# PlantMonitor.net
KiCad netlist of a schematic drawn in EAGLE
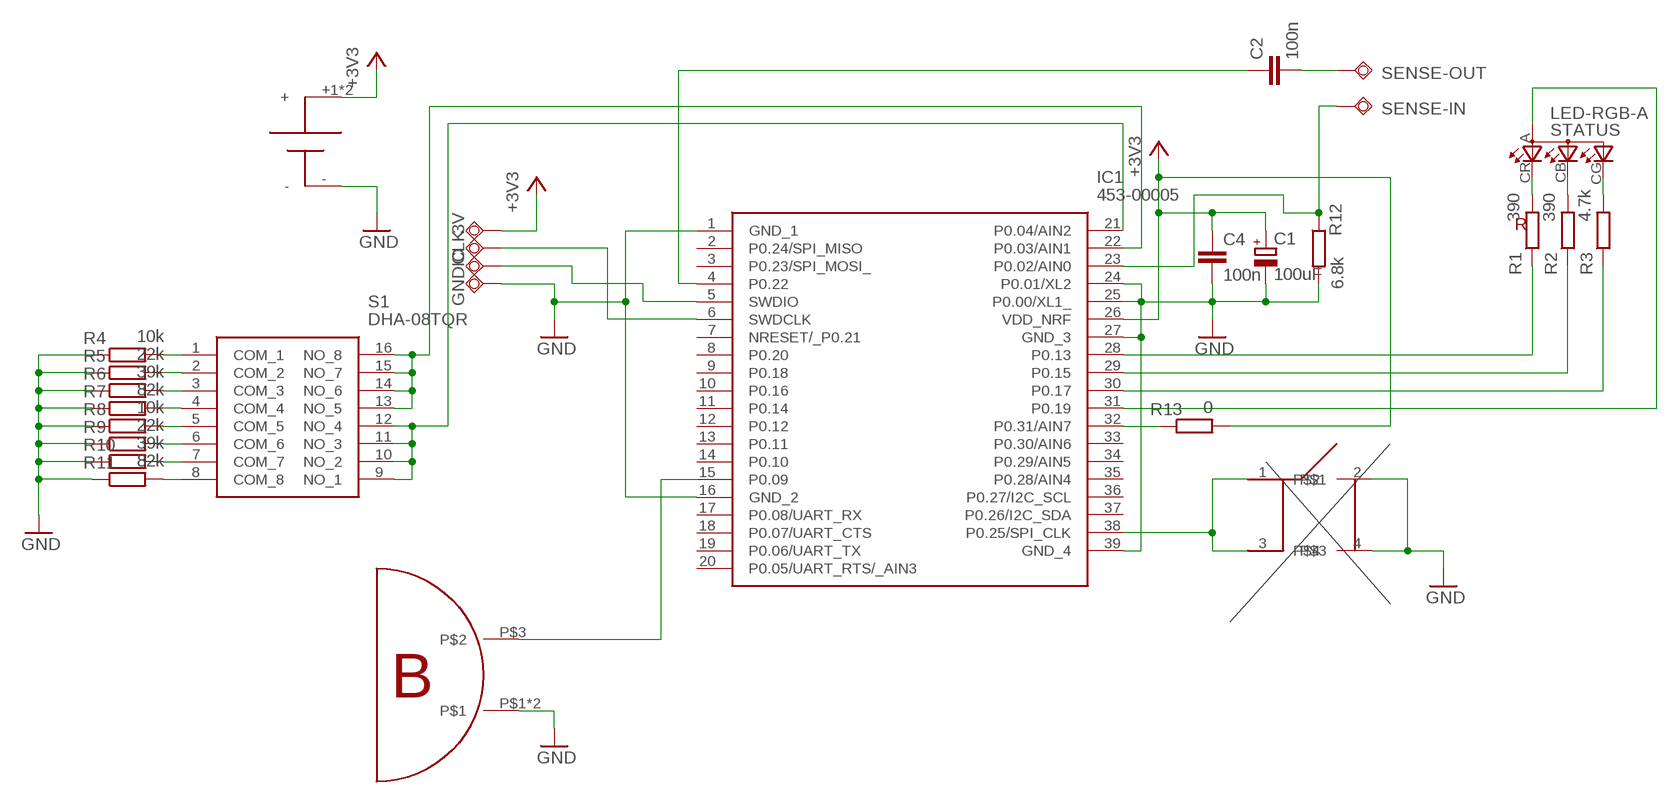
[diagram p0: schematic, sheet 1]

(export (version "E")
  (design (tool "Eeschema 10.0.6"))
  (components
    (comp (ref "3V")
      (value "TPSQB1,27")
      (footprint "eagle-import:B1,27")
      (libsource (lib "eagle-import") (part "TPSQB1,27"))
    )
    (comp (ref "C1")
      (value "100uF")
      (footprint "eagle-import:A_3216-18W")
      (libsource (lib "eagle-import") (part "CPOL-EUA/3216-18W"))
    )
    (comp (ref "C2")
      (value "100n")
      (footprint "eagle-import:C0603K")
      (libsource (lib "eagle-import") (part "C-EUC0603K"))
    )
    (comp (ref "C4")
      (value "100n")
      (footprint "eagle-import:C0603K")
      (libsource (lib "eagle-import") (part "C-EUC0603K"))
    )
    (comp (ref "CLK")
      (value "TPSQB1,27")
      (footprint "eagle-import:B1,27")
      (libsource (lib "eagle-import") (part "TPSQB1,27"))
    )
    (comp (ref "GND")
      (value "TPSQB1,27")
      (footprint "eagle-import:B1,27")
      (libsource (lib "eagle-import") (part "TPSQB1,27"))
    )
    (comp (ref "IC1")
      (value "453-00005")
      (footprint "eagle-import:45300005")
      (fields (field (name "MOUSER_PART_NUMBER") "239-453-00005"))
      (libsource (lib "eagle-import") (part "453-00005"))
    )
    (comp (ref "IO")
      (value "TPSQB1,27")
      (footprint "eagle-import:B1,27")
      (libsource (lib "eagle-import") (part "TPSQB1,27"))
    )
    (comp (ref "R1")
      (value "390")
      (footprint "eagle-import:R0603")
      (libsource (lib "eagle-import") (part "R-EU_R0603"))
    )
    (comp (ref "R2")
      (value "390")
      (footprint "eagle-import:R0603")
      (libsource (lib "eagle-import") (part "R-EU_R0603"))
    )
    (comp (ref "R3")
      (value "4.7k")
      (footprint "eagle-import:R0603")
      (libsource (lib "eagle-import") (part "R-EU_R0603"))
    )
    (comp (ref "R4")
      (value "10k")
      (footprint "eagle-import:R0603")
      (libsource (lib "eagle-import") (part "R-EU_R0603"))
    )
    (comp (ref "R5")
      (value "22k")
      (footprint "eagle-import:R0603")
      (libsource (lib "eagle-import") (part "R-EU_R0603"))
    )
    (comp (ref "R6")
      (value "39k")
      (footprint "eagle-import:R0603")
      (libsource (lib "eagle-import") (part "R-EU_R0603"))
    )
    (comp (ref "R7")
      (value "82k")
      (footprint "eagle-import:R0603")
      (libsource (lib "eagle-import") (part "R-EU_R0603"))
    )
    (comp (ref "R8")
      (value "10k")
      (footprint "eagle-import:R0603")
      (libsource (lib "eagle-import") (part "R-EU_R0603"))
    )
    (comp (ref "R9")
      (value "22k")
      (footprint "eagle-import:R0603")
      (libsource (lib "eagle-import") (part "R-EU_R0603"))
    )
    (comp (ref "R10")
      (value "39k")
      (footprint "eagle-import:R0603")
      (libsource (lib "eagle-import") (part "R-EU_R0603"))
    )
    (comp (ref "R11")
      (value "82k")
      (footprint "eagle-import:R0603")
      (libsource (lib "eagle-import") (part "R-EU_R0603"))
    )
    (comp (ref "R12")
      (value "6.8k")
      (footprint "eagle-import:R0603")
      (libsource (lib "eagle-import") (part "R-EU_R0603"))
    )
    (comp (ref "R13")
      (value "0")
      (footprint "eagle-import:R0603")
      (libsource (lib "eagle-import") (part "R-EU_R0603"))
    )
    (comp (ref "S1")
      (value "DHA-08TQR")
      (footprint "eagle-import:SOIC127P810X230-16N")
      (fields (field (name "MOUSER_PART_NUMBER") "113-DHA08TQR"))
      (libsource (lib "eagle-import") (part "DHA-08TQR"))
    )
    (comp (ref "SENSE-IN")
      (value "TPSQB1,27")
      (footprint "eagle-import:B1,27")
      (libsource (lib "eagle-import") (part "TPSQB1,27"))
    )
    (comp (ref "SENSE-OUT")
      (value "TPSQB1,27")
      (footprint "eagle-import:B1,27")
      (libsource (lib "eagle-import") (part "TPSQB1,27"))
    )
    (comp (ref "STATUS")
      (value "LED-RGB-A")
      (footprint "eagle-import:LED-RGB-A")
      (libsource (lib "eagle-import") (part "LED-RGB-A"))
    )
    (comp (ref "U$1")
      (value "PTS525SK08SMTR2LFS")
      (footprint "eagle-import:PTS525SK08SMTR2LFS")
      (libsource (lib "eagle-import") (part "PTS525SK08SMTR2LFS"))
    )
    (comp (ref "U$2")
      (value "COIN-CELL-HOLDER")
      (footprint "eagle-import:COIN-CELL-HOLDER")
      (libsource (lib "eagle-import") (part "COIN-CELL-HOLDER"))
    )
    (comp (ref "U$3")
      (value "MICRO-BUZZER")
      (footprint "eagle-import:MICRO-BUZZER")
      (libsource (lib "eagle-import") (part "MICRO-BUZZER"))
    )
  )
  (nets
    (net (code "1") (name "+3V3") (class "Default")
      (node (ref "3V") (pin "TP") (pinfunction "TP_TP") (pintype "input"))
      (node (ref "C1") (pin "+") (pinfunction "+_+") (pintype "passive"))
      (node (ref "C4") (pin "1") (pinfunction "1_1") (pintype "passive"))
      (node (ref "IC1") (pin "26") (pinfunction "VDD_NRF_26") (pintype "bidirectional"))
      (node (ref "R13") (pin "2") (pinfunction "2_2") (pintype "passive"))
      (node (ref "U$2") (pin "+1") (pinfunction "+_+1") (pintype "bidirectional"))
      (node (ref "U$2") (pin "+2") (pinfunction "+_+2") (pintype "bidirectional"))
    )
    (net (code "2") (name "GND") (class "Default")
      (node (ref "C1") (pin "-") (pinfunction "-_-") (pintype "passive"))
      (node (ref "C4") (pin "2") (pinfunction "2_2") (pintype "passive"))
      (node (ref "GND") (pin "TP") (pinfunction "TP_TP") (pintype "input"))
      (node (ref "IC1") (pin "1") (pinfunction "GND_1_1") (pintype "bidirectional"))
      (node (ref "IC1") (pin "16") (pinfunction "GND_2_16") (pintype "bidirectional"))
      (node (ref "IC1") (pin "24") (pinfunction "P0.01/XL2_24") (pintype "bidirectional"))
      (node (ref "IC1") (pin "25") (pinfunction "P0.00/XL1__25") (pintype "bidirectional"))
      (node (ref "IC1") (pin "27") (pinfunction "GND_3_27") (pintype "bidirectional"))
      (node (ref "IC1") (pin "39") (pinfunction "GND_4_39") (pintype "bidirectional"))
      (node (ref "R10") (pin "1") (pinfunction "1_1") (pintype "passive"))
      (node (ref "R11") (pin "1") (pinfunction "1_1") (pintype "passive"))
      (node (ref "R12") (pin "2") (pinfunction "2_2") (pintype "passive"))
      (node (ref "R4") (pin "1") (pinfunction "1_1") (pintype "passive"))
      (node (ref "R5") (pin "1") (pinfunction "1_1") (pintype "passive"))
      (node (ref "R6") (pin "1") (pinfunction "1_1") (pintype "passive"))
      (node (ref "R7") (pin "1") (pinfunction "1_1") (pintype "passive"))
      (node (ref "R8") (pin "1") (pinfunction "1_1") (pintype "passive"))
      (node (ref "R9") (pin "1") (pinfunction "1_1") (pintype "passive"))
      (node (ref "U$1") (pin "2") (pinfunction "P$2_2") (pintype "bidirectional"))
      (node (ref "U$1") (pin "4") (pinfunction "P$4_4") (pintype "bidirectional"))
      (node (ref "U$2") (pin "-") (pinfunction "-_-") (pintype "bidirectional"))
      (node (ref "U$3") (pin "P$1") (pinfunction "P$1_P$1") (pintype "bidirectional"))
      (node (ref "U$3") (pin "P$2") (pinfunction "P$1_P$2") (pintype "bidirectional"))
    )
    (net (code "3") (name "Net-(C2-Pad2)") (class "Default")
      (node (ref "C2") (pin "2") (pinfunction "2_2") (pintype "passive"))
      (node (ref "SENSE-OUT") (pin "TP") (pinfunction "TP_TP") (pintype "input"))
    )
    (net (code "4") (name "Net-(IC1-P0.02{slash}AIN0)") (class "Default")
      (node (ref "IC1") (pin "23") (pinfunction "P0.02/AIN0_23") (pintype "bidirectional"))
      (node (ref "R12") (pin "1") (pinfunction "1_1") (pintype "passive"))
      (node (ref "SENSE-IN") (pin "TP") (pinfunction "TP_TP") (pintype "input"))
    )
    (net (code "5") (name "Net-(IC1-P0.03{slash}AIN1)") (class "Default")
      (node (ref "IC1") (pin "22") (pinfunction "P0.03/AIN1_22") (pintype "bidirectional"))
      (node (ref "S1") (pin "13") (pinfunction "NO_5_13") (pintype "bidirectional"))
      (node (ref "S1") (pin "14") (pinfunction "NO_6_14") (pintype "bidirectional"))
      (node (ref "S1") (pin "15") (pinfunction "NO_7_15") (pintype "bidirectional"))
      (node (ref "S1") (pin "16") (pinfunction "NO_8_16") (pintype "bidirectional"))
    )
    (net (code "6") (name "Net-(IC1-P0.04{slash}AIN2)") (class "Default")
      (node (ref "IC1") (pin "21") (pinfunction "P0.04/AIN2_21") (pintype "bidirectional"))
      (node (ref "S1") (pin "10") (pinfunction "NO_2_10") (pintype "bidirectional"))
      (node (ref "S1") (pin "11") (pinfunction "NO_3_11") (pintype "bidirectional"))
      (node (ref "S1") (pin "12") (pinfunction "NO_4_12") (pintype "bidirectional"))
      (node (ref "S1") (pin "9") (pinfunction "NO_1_9") (pintype "bidirectional"))
    )
    (net (code "7") (name "Net-(IC1-P0.09)") (class "Default")
      (node (ref "IC1") (pin "15") (pinfunction "P0.09_15") (pintype "bidirectional"))
      (node (ref "U$3") (pin "P$3") (pinfunction "P$2_P$3") (pintype "bidirectional"))
    )
    (net (code "8") (name "Net-(IC1-P0.13)") (class "Default")
      (node (ref "IC1") (pin "28") (pinfunction "P0.13_28") (pintype "bidirectional"))
      (node (ref "R1") (pin "1") (pinfunction "1_1") (pintype "passive"))
    )
    (net (code "9") (name "Net-(IC1-P0.15)") (class "Default")
      (node (ref "IC1") (pin "29") (pinfunction "P0.15_29") (pintype "bidirectional"))
      (node (ref "R2") (pin "1") (pinfunction "1_1") (pintype "passive"))
    )
    (net (code "10") (name "Net-(IC1-P0.17)") (class "Default")
      (node (ref "IC1") (pin "30") (pinfunction "P0.17_30") (pintype "bidirectional"))
      (node (ref "R3") (pin "1") (pinfunction "1_1") (pintype "passive"))
    )
    (net (code "11") (name "Net-(IC1-P0.19)") (class "Default")
      (node (ref "IC1") (pin "31") (pinfunction "P0.19_31") (pintype "bidirectional"))
      (node (ref "STATUS") (pin "A") (pinfunction "A_A") (pintype "passive"))
    )
    (net (code "12") (name "Net-(IC1-P0.22)") (class "Default")
      (node (ref "C2") (pin "1") (pinfunction "1_1") (pintype "passive"))
      (node (ref "IC1") (pin "4") (pinfunction "P0.22_4") (pintype "bidirectional"))
    )
    (net (code "13") (name "Net-(IC1-P0.25{slash}SPI_CLK)") (class "Default")
      (node (ref "IC1") (pin "38") (pinfunction "P0.25/SPI_CLK_38") (pintype "bidirectional"))
      (node (ref "U$1") (pin "1") (pinfunction "P$1_1") (pintype "bidirectional"))
      (node (ref "U$1") (pin "3") (pinfunction "P$3_3") (pintype "bidirectional"))
    )
    (net (code "14") (name "Net-(IC1-P0.31{slash}AIN7)") (class "Default")
      (node (ref "IC1") (pin "32") (pinfunction "P0.31/AIN7_32") (pintype "bidirectional"))
      (node (ref "R13") (pin "1") (pinfunction "1_1") (pintype "passive"))
    )
    (net (code "15") (name "Net-(IC1-SWDCLK)") (class "Default")
      (node (ref "CLK") (pin "TP") (pinfunction "TP_TP") (pintype "input"))
      (node (ref "IC1") (pin "6") (pinfunction "SWDCLK_6") (pintype "bidirectional"))
    )
    (net (code "16") (name "Net-(IC1-SWDIO)") (class "Default")
      (node (ref "IC1") (pin "5") (pinfunction "SWDIO_5") (pintype "bidirectional"))
      (node (ref "IO") (pin "TP") (pinfunction "TP_TP") (pintype "input"))
    )
    (net (code "17") (name "Net-(S1-COM_1)") (class "Default")
      (node (ref "R4") (pin "2") (pinfunction "2_2") (pintype "passive"))
      (node (ref "S1") (pin "1") (pinfunction "COM_1_1") (pintype "bidirectional"))
    )
    (net (code "18") (name "Net-(S1-COM_2)") (class "Default")
      (node (ref "R5") (pin "2") (pinfunction "2_2") (pintype "passive"))
      (node (ref "S1") (pin "2") (pinfunction "COM_2_2") (pintype "bidirectional"))
    )
    (net (code "19") (name "Net-(S1-COM_3)") (class "Default")
      (node (ref "R6") (pin "2") (pinfunction "2_2") (pintype "passive"))
      (node (ref "S1") (pin "3") (pinfunction "COM_3_3") (pintype "bidirectional"))
    )
    (net (code "20") (name "Net-(S1-COM_4)") (class "Default")
      (node (ref "R7") (pin "2") (pinfunction "2_2") (pintype "passive"))
      (node (ref "S1") (pin "4") (pinfunction "COM_4_4") (pintype "bidirectional"))
    )
    (net (code "21") (name "Net-(S1-COM_5)") (class "Default")
      (node (ref "R8") (pin "2") (pinfunction "2_2") (pintype "passive"))
      (node (ref "S1") (pin "5") (pinfunction "COM_5_5") (pintype "bidirectional"))
    )
    (net (code "22") (name "Net-(S1-COM_6)") (class "Default")
      (node (ref "R9") (pin "2") (pinfunction "2_2") (pintype "passive"))
      (node (ref "S1") (pin "6") (pinfunction "COM_6_6") (pintype "bidirectional"))
    )
    (net (code "23") (name "Net-(S1-COM_7)") (class "Default")
      (node (ref "R10") (pin "2") (pinfunction "2_2") (pintype "passive"))
      (node (ref "S1") (pin "7") (pinfunction "COM_7_7") (pintype "bidirectional"))
    )
    (net (code "24") (name "Net-(S1-COM_8)") (class "Default")
      (node (ref "R11") (pin "2") (pinfunction "2_2") (pintype "passive"))
      (node (ref "S1") (pin "8") (pinfunction "COM_8_8") (pintype "bidirectional"))
    )
    (net (code "25") (name "Net-(STATUS-CBLUE)") (class "Default")
      (node (ref "R2") (pin "2") (pinfunction "2_2") (pintype "passive"))
      (node (ref "STATUS") (pin "CB") (pinfunction "CBLUE_CB") (pintype "passive"))
    )
    (net (code "26") (name "Net-(STATUS-CGREEN)") (class "Default")
      (node (ref "R3") (pin "2") (pinfunction "2_2") (pintype "passive"))
      (node (ref "STATUS") (pin "CG") (pinfunction "CGREEN_CG") (pintype "passive"))
    )
    (net (code "27") (name "Net-(STATUS-CRED)") (class "Default")
      (node (ref "R1") (pin "2") (pinfunction "2_2") (pintype "passive"))
      (node (ref "STATUS") (pin "CR") (pinfunction "CRED_CR") (pintype "passive"))
    )
    (net (code "28") (name "unconnected-(IC1-NRESET{slash}_P0.21-Pad7)") (class "Default")
      (node (ref "IC1") (pin "7") (pinfunction "NRESET/_P0.21_7") (pintype "bidirectional"))
    )
    (net (code "29") (name "unconnected-(IC1-P0.05{slash}UART_RTS{slash}_AIN3-Pad20)") (class "Default")
      (node (ref "IC1") (pin "20") (pinfunction "P0.05/UART_RTS/_AIN3_20") (pintype "bidirectional"))
    )
    (net (code "30") (name "unconnected-(IC1-P0.06{slash}UART_TX-Pad19)") (class "Default")
      (node (ref "IC1") (pin "19") (pinfunction "P0.06/UART_TX_19") (pintype "bidirectional"))
    )
    (net (code "31") (name "unconnected-(IC1-P0.07{slash}UART_CTS-Pad18)") (class "Default")
      (node (ref "IC1") (pin "18") (pinfunction "P0.07/UART_CTS_18") (pintype "bidirectional"))
    )
    (net (code "32") (name "unconnected-(IC1-P0.08{slash}UART_RX-Pad17)") (class "Default")
      (node (ref "IC1") (pin "17") (pinfunction "P0.08/UART_RX_17") (pintype "bidirectional"))
    )
    (net (code "33") (name "unconnected-(IC1-P0.10-Pad14)") (class "Default")
      (node (ref "IC1") (pin "14") (pinfunction "P0.10_14") (pintype "bidirectional"))
    )
    (net (code "34") (name "unconnected-(IC1-P0.11-Pad13)") (class "Default")
      (node (ref "IC1") (pin "13") (pinfunction "P0.11_13") (pintype "bidirectional"))
    )
    (net (code "35") (name "unconnected-(IC1-P0.12-Pad12)") (class "Default")
      (node (ref "IC1") (pin "12") (pinfunction "P0.12_12") (pintype "bidirectional"))
    )
    (net (code "36") (name "unconnected-(IC1-P0.14-Pad11)") (class "Default")
      (node (ref "IC1") (pin "11") (pinfunction "P0.14_11") (pintype "bidirectional"))
    )
    (net (code "37") (name "unconnected-(IC1-P0.16-Pad10)") (class "Default")
      (node (ref "IC1") (pin "10") (pinfunction "P0.16_10") (pintype "bidirectional"))
    )
    (net (code "38") (name "unconnected-(IC1-P0.18-Pad9)") (class "Default")
      (node (ref "IC1") (pin "9") (pinfunction "P0.18_9") (pintype "bidirectional"))
    )
    (net (code "39") (name "unconnected-(IC1-P0.20-Pad8)") (class "Default")
      (node (ref "IC1") (pin "8") (pinfunction "P0.20_8") (pintype "bidirectional"))
    )
    (net (code "40") (name "unconnected-(IC1-P0.23{slash}SPI_MOSI_-Pad3)") (class "Default")
      (node (ref "IC1") (pin "3") (pinfunction "P0.23/SPI_MOSI__3") (pintype "bidirectional"))
    )
    (net (code "41") (name "unconnected-(IC1-P0.24{slash}SPI_MISO-Pad2)") (class "Default")
      (node (ref "IC1") (pin "2") (pinfunction "P0.24/SPI_MISO_2") (pintype "bidirectional"))
    )
    (net (code "42") (name "unconnected-(IC1-P0.26{slash}I2C_SDA-Pad37)") (class "Default")
      (node (ref "IC1") (pin "37") (pinfunction "P0.26/I2C_SDA_37") (pintype "bidirectional"))
    )
    (net (code "43") (name "unconnected-(IC1-P0.27{slash}I2C_SCL-Pad36)") (class "Default")
      (node (ref "IC1") (pin "36") (pinfunction "P0.27/I2C_SCL_36") (pintype "bidirectional"))
    )
    (net (code "44") (name "unconnected-(IC1-P0.28{slash}AIN4-Pad35)") (class "Default")
      (node (ref "IC1") (pin "35") (pinfunction "P0.28/AIN4_35") (pintype "bidirectional"))
    )
    (net (code "45") (name "unconnected-(IC1-P0.29{slash}AIN5-Pad34)") (class "Default")
      (node (ref "IC1") (pin "34") (pinfunction "P0.29/AIN5_34") (pintype "bidirectional"))
    )
    (net (code "46") (name "unconnected-(IC1-P0.30{slash}AIN6-Pad33)") (class "Default")
      (node (ref "IC1") (pin "33") (pinfunction "P0.30/AIN6_33") (pintype "bidirectional"))
    )
  )
)
